# Sheet1.net
KiCad netlist of a schematic drawn in Altium Designer
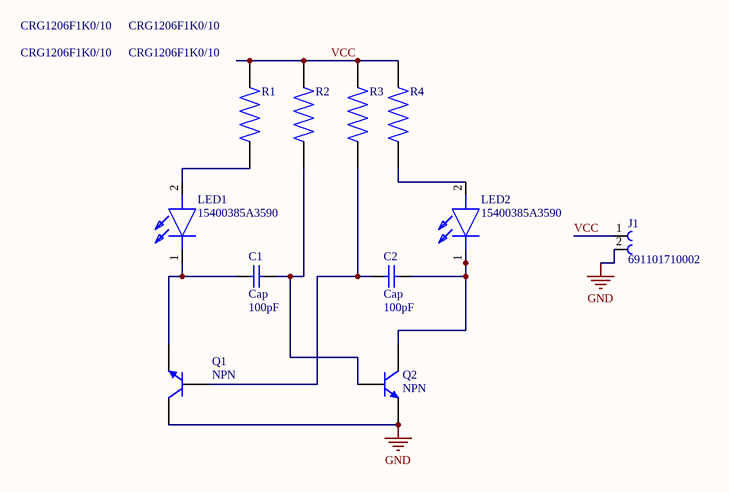
[diagram p0: Sheet1.SchDoc]

(export (version "E")
  (design (tool "Eeschema 10.0.6"))
  (components
    (comp (ref "C1")
      (value "Cap")
      (footprint "RAD-0.3")
      (description "Capacitor")
      (fields (field (name "ALTIUM_VALUE") "100pF") (field (name "PUBLISHER") "Altium Limited"))
      (libsource (lib "Miscellaneous Devices") (part "Cap"))
    )
    (comp (ref "C2")
      (value "Cap")
      (footprint "RAD-0.3")
      (description "Capacitor")
      (fields (field (name "ALTIUM_VALUE") "100pF") (field (name "PUBLISHER") "Altium Limited"))
      (libsource (lib "Miscellaneous Devices") (part "Cap"))
    )
    (comp (ref "J1")
      (value "691101710002")
      (footprint "691101710002")
      (description "2 Position Wire to Board Terminal Block Horizontal with Board 0.197 (5.00mm) Through Hole")
      (fields (field (name "MF") "WÃ¼rth Elektronik"))
      (libsource (lib "691101710002") (part "691101710002"))
    )
    (comp (ref "LED1")
      (value "15400385A3590")
      (footprint "SamacSys:15400385A3590")
      (description "LED")
      (fields (field (name "MOUSER PART NUMBER") "710-15400385A3590"))
      (libsource (lib "SamacSys") (part "15400385A3590"))
    )
    (comp (ref "LED2")
      (value "15400385A3590")
      (footprint "SamacSys:15400385A3590")
      (description "LED")
      (fields (field (name "MOUSER PART NUMBER") "710-15400385A3590"))
      (libsource (lib "SamacSys") (part "15400385A3590"))
    )
    (comp (ref "Q1")
      (value "NPN")
      (footprint "TO-226-AA")
      (description "NPN Bipolar Transistor")
      (fields (field (name "PUBLISHER") "Altium Limited"))
      (libsource (lib "Miscellaneous Devices") (part "NPN"))
    )
    (comp (ref "Q2")
      (value "NPN")
      (footprint "TO-226-AA")
      (description "NPN Bipolar Transistor")
      (fields (field (name "PUBLISHER") "Altium Limited"))
      (libsource (lib "Miscellaneous Devices") (part "NPN"))
    )
    (comp (ref "R1")
      (value "CRG1206F1K0/10")
      (footprint "RESC3115X65N")
      (description "Res Kal谋n Film 1206 1K Ohm 1% 1 / 4W 卤 100ppm / 掳 C Kal谋pl谋 SMD SMD")
      (fields (field (name "TOLERANCE") "1%") (field (name "MF") "TE Connectivity"))
      (libsource (lib "CRG1206F1K0_10") (part "CRG1206F1K0/10"))
    )
    (comp (ref "R2")
      (value "CRG1206F1K0/10")
      (footprint "RESC3115X65N")
      (description "Res Kal谋n Film 1206 1K Ohm 1% 1 / 4W 卤 100ppm / 掳 C Kal谋pl谋 SMD SMD")
      (fields (field (name "TOLERANCE") "1%") (field (name "MF") "TE Connectivity"))
      (libsource (lib "CRG1206F1K0_10") (part "CRG1206F1K0/10"))
    )
    (comp (ref "R3")
      (value "CRG1206F1K0/10")
      (footprint "RESC3115X65N")
      (description "Res Kal谋n Film 1206 1K Ohm 1% 1 / 4W 卤 100ppm / 掳 C Kal谋pl谋 SMD SMD")
      (fields (field (name "TOLERANCE") "1%") (field (name "MF") "TE Connectivity"))
      (libsource (lib "CRG1206F1K0_10") (part "CRG1206F1K0/10"))
    )
    (comp (ref "R4")
      (value "CRG1206F1K0/10")
      (footprint "RESC3115X65N")
      (description "Res Kal谋n Film 1206 1K Ohm 1% 1 / 4W 卤 100ppm / 掳 C Kal谋pl谋 SMD SMD")
      (fields (field (name "TOLERANCE") "1%") (field (name "MF") "TE Connectivity"))
      (libsource (lib "CRG1206F1K0_10") (part "CRG1206F1K0/10"))
    )
  )
  (nets
    (net (code "1") (name "/VCC") (class "Default")
      (node (ref "J1") (pin "1") (pinfunction "1_1") (pintype "passive"))
      (node (ref "R1") (pin "2") (pinfunction "2_2") (pintype "passive"))
      (node (ref "R2") (pin "2") (pinfunction "2_2") (pintype "passive"))
      (node (ref "R3") (pin "2") (pinfunction "2_2") (pintype "passive"))
      (node (ref "R4") (pin "2") (pinfunction "2_2") (pintype "passive"))
    )
    (net (code "2") (name "GND") (class "Default")
      (node (ref "J1") (pin "2") (pinfunction "2_2") (pintype "passive"))
      (node (ref "Q1") (pin "1") (pinfunction "C_1") (pintype "passive"))
      (node (ref "Q2") (pin "3") (pinfunction "E_3") (pintype "passive"))
    )
    (net (code "3") (name "Net-(LED1-A)") (class "Default")
      (node (ref "LED1") (pin "2") (pinfunction "A_2") (pintype "passive"))
      (node (ref "R1") (pin "1") (pinfunction "1_1") (pintype "passive"))
    )
    (net (code "4") (name "Net-(LED1-K)") (class "Default")
      (node (ref "C1") (pin "1") (pinfunction "1_1") (pintype "passive"))
      (node (ref "LED1") (pin "1") (pinfunction "K_1") (pintype "passive"))
      (node (ref "Q1") (pin "3") (pinfunction "E_3") (pintype "passive"))
    )
    (net (code "5") (name "Net-(LED2-A)") (class "Default")
      (node (ref "LED2") (pin "2") (pinfunction "A_2") (pintype "passive"))
      (node (ref "R4") (pin "1") (pinfunction "1_1") (pintype "passive"))
    )
    (net (code "6") (name "Net-(LED2-K)") (class "Default")
      (node (ref "C2") (pin "2") (pinfunction "2_2") (pintype "passive"))
      (node (ref "LED2") (pin "1") (pinfunction "K_1") (pintype "passive"))
      (node (ref "Q2") (pin "1") (pinfunction "C_1") (pintype "passive"))
    )
    (net (code "7") (name "Net-(Q1-B)") (class "Default")
      (node (ref "C2") (pin "1") (pinfunction "1_1") (pintype "passive"))
      (node (ref "Q1") (pin "2") (pinfunction "B_2") (pintype "passive"))
      (node (ref "R3") (pin "1") (pinfunction "1_1") (pintype "passive"))
    )
    (net (code "8") (name "Net-(Q2-B)") (class "Default")
      (node (ref "C1") (pin "2") (pinfunction "2_2") (pintype "passive"))
      (node (ref "Q2") (pin "2") (pinfunction "B_2") (pintype "passive"))
      (node (ref "R2") (pin "1") (pinfunction "1_1") (pintype "passive"))
    )
  )
)
